# RP2040.net
KiCad netlist of a schematic drawn in Altium Designer
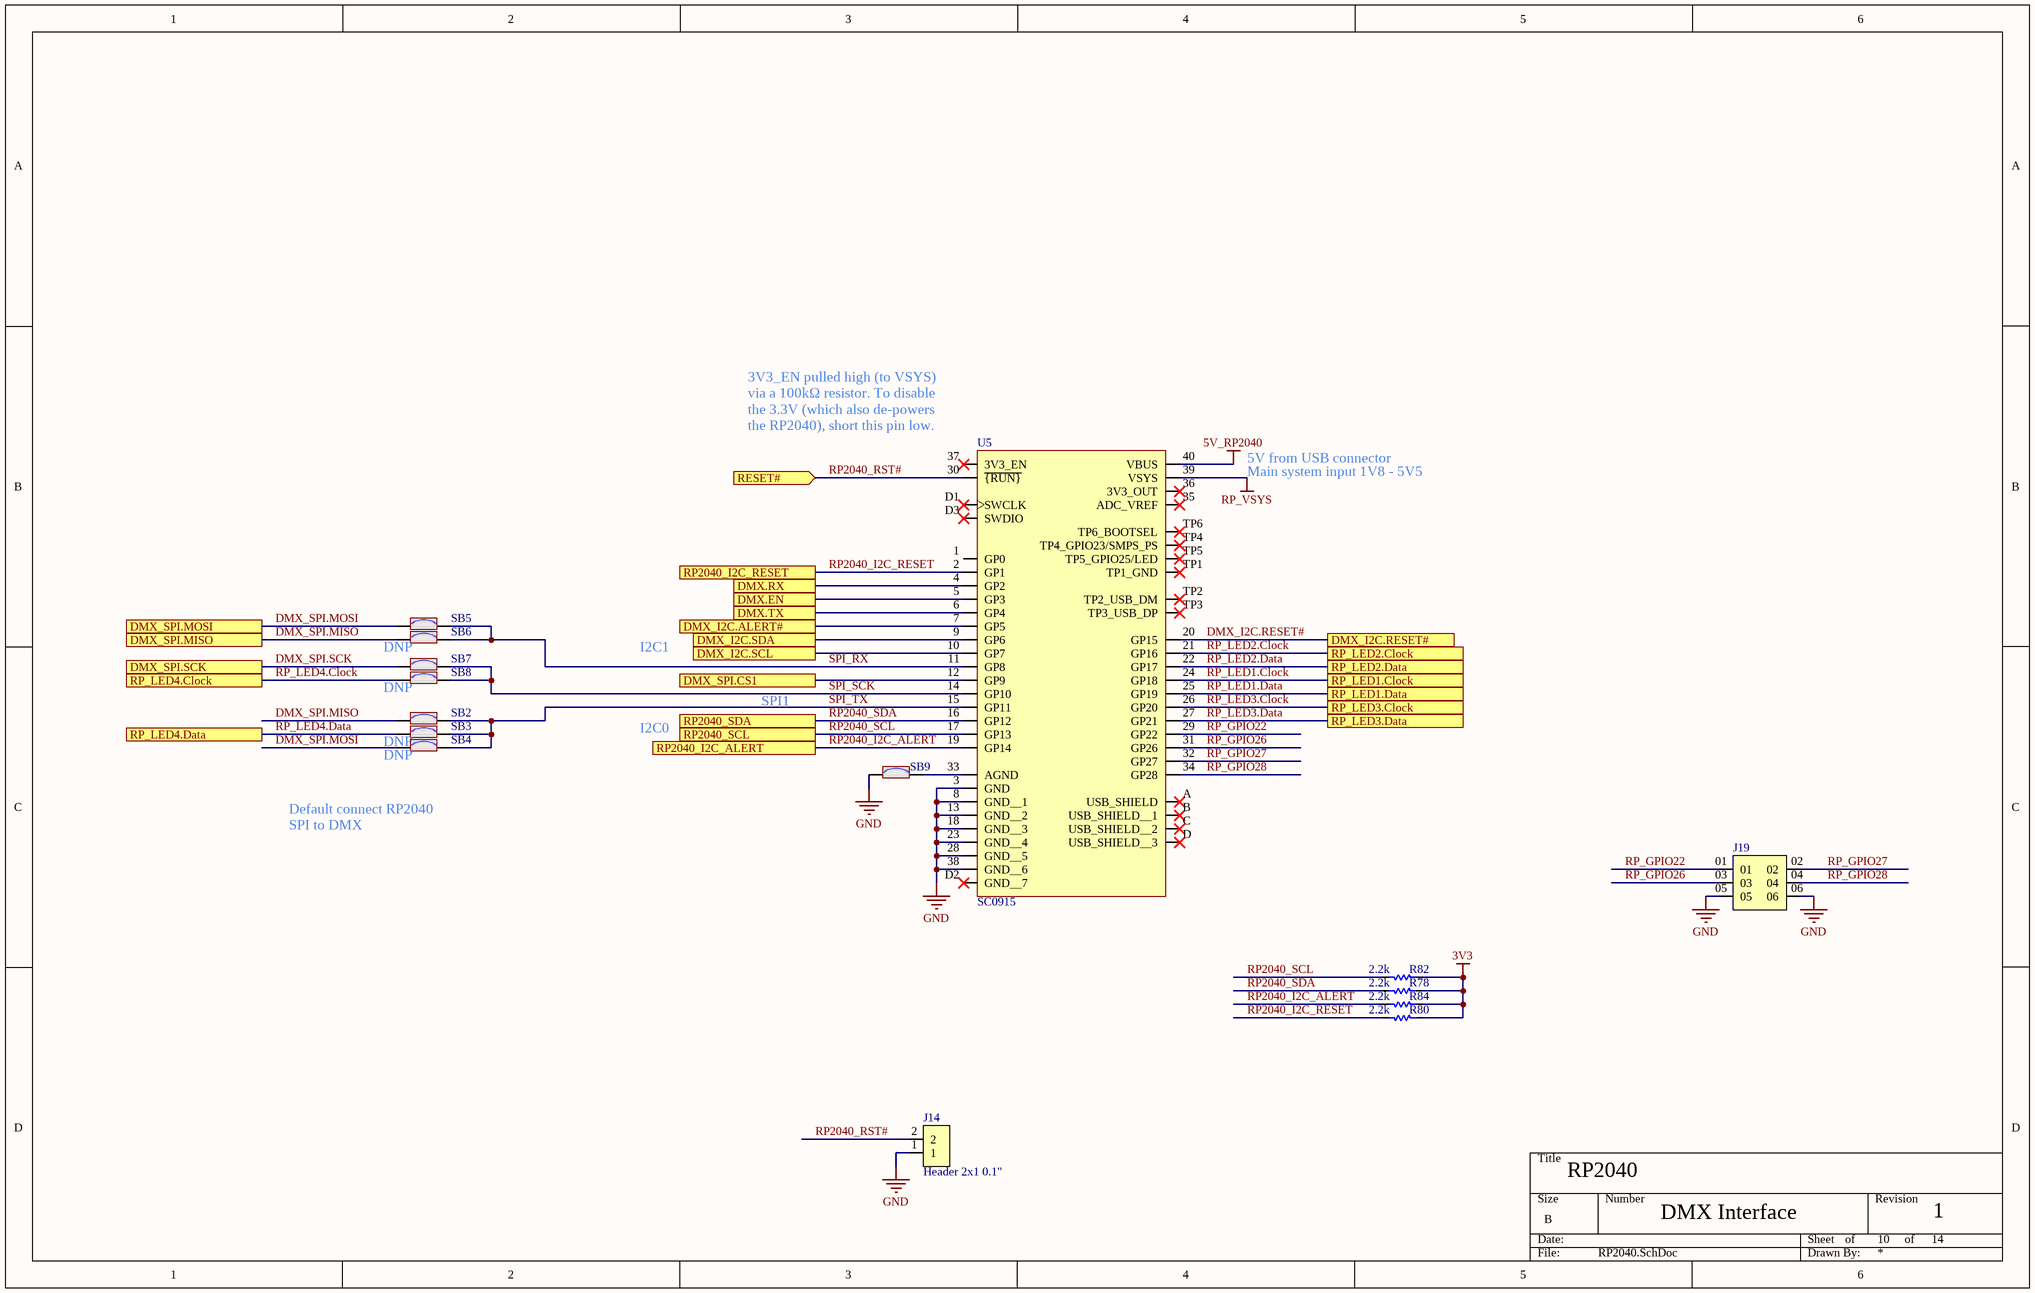
[diagram p0: RP2040.SchDoc]

(export (version "E")
  (design (tool "Eeschema 10.0.6"))
  (components
    (comp (ref "J14")
      (value "Header 2x1 0.1\"")
      (footprint "FP-M20-9990245-MFG")
      (description "Conn Header Vert 2POS 2.54MM")
      (libsource (lib "Equus Computer Systems") (part "HEADER-2x1"))
    )
    (comp (ref "J19")
      (value "Header 3x2 0.1\"")
      (footprint "HEADER 3x2 0.1 Through hole")
      (description "Board Connector Tall, 6 Contact(s), 2 Row(s), Male, Straight, 0.1 inch Pitch")
      (libsource (lib "Equus Computer Systems") (part "Header 3x2 0.1{dblquote}"))
    )
    (comp (ref "R78")
      (value "2.2k")
      (footprint "RESC1608X06N_0603_MED")
      (fields
        (field (name "TOLERANCE") "1%")
        (field (name "POWER") "100mW")
        (field (name "Comment") "RC0603FR-072K2L")
      )
      (libsource (lib "Equus Computer Systems") (part "RES-2"))
    )
    (comp (ref "R80")
      (value "2.2k")
      (footprint "RESC1608X06N_0603_MED")
      (fields
        (field (name "TOLERANCE") "1%")
        (field (name "POWER") "100mW")
        (field (name "Comment") "RC0603FR-072K2L")
      )
      (libsource (lib "Equus Computer Systems") (part "RES-2"))
    )
    (comp (ref "R82")
      (value "2.2k")
      (footprint "RESC1608X06N_0603_MED")
      (fields
        (field (name "TOLERANCE") "1%")
        (field (name "POWER") "100mW")
        (field (name "Comment") "RC0603FR-072K2L")
      )
      (libsource (lib "Equus Computer Systems") (part "RES-2"))
    )
    (comp (ref "R84")
      (value "2.2k")
      (footprint "RESC1608X06N_0603_MED")
      (fields
        (field (name "TOLERANCE") "1%")
        (field (name "POWER") "100mW")
        (field (name "Comment") "RC0603FR-072K2L")
      )
      (libsource (lib "Equus Computer Systems") (part "RES-2"))
    )
    (comp (ref "SB2")
      (value "SolderBridge0603_On")
      (footprint "SOLDER-BRIDGE_R0603-0R-CLOSEMASK")
      (description "Solder Bridge ON")
      (fields
        (field (name "INTERNAL_PART_NUMBER") "MCD-00071")
        (field (name "MANUFACTURER") "YAGEO")
        (field (name "PROVIDED_BY") "SUBCO")
      )
      (libsource (lib "Equus Computer Systems") (part "SolderBridge0603_On"))
    )
    (comp (ref "SB3")
      (value "SolderBridge0603_On")
      (footprint "SOLDER-BRIDGE_R0603-0R-CLOSEMASK")
      (description "Solder Bridge ON")
      (fields
        (field (name "INTERNAL_PART_NUMBER") "MCD-00071")
        (field (name "MANUFACTURER") "YAGEO")
        (field (name "PROVIDED_BY") "SUBCO")
      )
      (libsource (lib "Equus Computer Systems") (part "SolderBridge0603_On"))
    )
    (comp (ref "SB4")
      (value "SolderBridge0603_On")
      (footprint "SOLDER-BRIDGE_R0603-0R-CLOSEMASK")
      (description "Solder Bridge ON")
      (fields
        (field (name "INTERNAL_PART_NUMBER") "MCD-00071")
        (field (name "MANUFACTURER") "YAGEO")
        (field (name "PROVIDED_BY") "SUBCO")
      )
      (libsource (lib "Equus Computer Systems") (part "SolderBridge0603_On"))
    )
    (comp (ref "SB5")
      (value "SolderBridge0603_On")
      (footprint "SOLDER-BRIDGE_R0603-0R-CLOSEMASK")
      (description "Solder Bridge ON")
      (fields
        (field (name "INTERNAL_PART_NUMBER") "MCD-00071")
        (field (name "MANUFACTURER") "YAGEO")
        (field (name "PROVIDED_BY") "SUBCO")
      )
      (libsource (lib "Equus Computer Systems") (part "SolderBridge0603_On"))
    )
    (comp (ref "SB6")
      (value "SolderBridge0603_On")
      (footprint "SOLDER-BRIDGE_R0603-0R-CLOSEMASK")
      (description "Solder Bridge ON")
      (fields
        (field (name "INTERNAL_PART_NUMBER") "MCD-00071")
        (field (name "MANUFACTURER") "YAGEO")
        (field (name "PROVIDED_BY") "SUBCO")
      )
      (libsource (lib "Equus Computer Systems") (part "SolderBridge0603_On"))
    )
    (comp (ref "SB7")
      (value "SolderBridge0603_On")
      (footprint "SOLDER-BRIDGE_R0603-0R-CLOSEMASK")
      (description "Solder Bridge ON")
      (fields
        (field (name "INTERNAL_PART_NUMBER") "MCD-00071")
        (field (name "MANUFACTURER") "YAGEO")
        (field (name "PROVIDED_BY") "SUBCO")
      )
      (libsource (lib "Equus Computer Systems") (part "SolderBridge0603_On"))
    )
    (comp (ref "SB8")
      (value "SolderBridge0603_On")
      (footprint "SOLDER-BRIDGE_R0603-0R-CLOSEMASK")
      (description "Solder Bridge ON")
      (fields
        (field (name "INTERNAL_PART_NUMBER") "MCD-00071")
        (field (name "MANUFACTURER") "YAGEO")
        (field (name "PROVIDED_BY") "SUBCO")
      )
      (libsource (lib "Equus Computer Systems") (part "SolderBridge0603_On"))
    )
    (comp (ref "SB9")
      (value "SolderBridge0603_On")
      (footprint "SOLDER-BRIDGE_R0603-0R")
      (description "Solder Bridge ON")
      (fields
        (field (name "INTERNAL_PART_NUMBER") "MCD-00071")
        (field (name "MANUFACTURER") "YAGEO")
        (field (name "PROVIDED_BY") "SUBCO")
      )
      (libsource (lib "Equus Computer Systems") (part "SolderBridge0603_On"))
    )
    (comp (ref "U5")
      (value "SC0915")
      (footprint "SC0915-Footprint-NoDEBUG")
      (description "RP2040 Pico ARM Cortex-M0+ - Microcontroller IC 32-Bit Dual-Core 133MHz")
      (fields (field (name "MF") "Raspberry Pi"))
      (libsource (lib "Equus Computer Systems") (part "SC0915-Symbol-1"))
    )
  )
  (nets
    (net (code "1") (name "/DMX.EN") (class "Default")
      (node (ref "U5") (pin "5") (pinfunction "GP3_5") (pintype "passive"))
    )
    (net (code "2") (name "/DMX.RX") (class "Default")
      (node (ref "U5") (pin "4") (pinfunction "GP2_4") (pintype "passive"))
    )
    (net (code "3") (name "/DMX.TX") (class "Default")
      (node (ref "U5") (pin "6") (pinfunction "GP4_6") (pintype "passive"))
    )
    (net (code "4") (name "/DMX_I2C.ALERT#") (class "Default")
      (node (ref "U5") (pin "7") (pinfunction "GP5_7") (pintype "passive"))
    )
    (net (code "5") (name "/DMX_I2C.RESET#") (class "Default")
      (node (ref "U5") (pin "20") (pinfunction "GP15_20") (pintype "passive"))
    )
    (net (code "6") (name "/DMX_I2C.SCL") (class "Default")
      (node (ref "U5") (pin "10") (pinfunction "GP7_10") (pintype "passive"))
    )
    (net (code "7") (name "/DMX_I2C.SDA") (class "Default")
      (node (ref "U5") (pin "9") (pinfunction "GP6_9") (pintype "passive"))
    )
    (net (code "8") (name "/DMX_SPI.CS1") (class "Default")
      (node (ref "U5") (pin "12") (pinfunction "GP9_12") (pintype "passive"))
    )
    (net (code "9") (name "/DMX_SPI.MISO") (class "Default")
      (node (ref "SB2") (pin "1") (pinfunction "1_1") (pintype "passive"))
      (node (ref "SB6") (pin "1") (pinfunction "1_1") (pintype "passive"))
    )
    (net (code "10") (name "/DMX_SPI.MOSI") (class "Default")
      (node (ref "SB4") (pin "1") (pinfunction "1_1") (pintype "passive"))
      (node (ref "SB5") (pin "1") (pinfunction "1_1") (pintype "passive"))
    )
    (net (code "11") (name "/DMX_SPI.SCK") (class "Default")
      (node (ref "SB7") (pin "1") (pinfunction "1_1") (pintype "passive"))
    )
    (net (code "12") (name "/RP2040_I2C_ALERT") (class "Default")
      (node (ref "R84") (pin "1") (pinfunction "1_1") (pintype "passive"))
      (node (ref "U5") (pin "19") (pinfunction "GP14_19") (pintype "passive"))
    )
    (net (code "13") (name "/RP2040_I2C_RESET") (class "Default")
      (node (ref "R80") (pin "1") (pinfunction "1_1") (pintype "passive"))
      (node (ref "U5") (pin "2") (pinfunction "GP1_2") (pintype "passive"))
    )
    (net (code "14") (name "/RP2040_RST#") (class "Default")
      (node (ref "J14") (pin "2") (pinfunction "2_2") (pintype "passive"))
      (node (ref "U5") (pin "30") (pinfunction "~{{RUN}}_30") (pintype "passive"))
    )
    (net (code "15") (name "/RP2040_SCL") (class "Default")
      (node (ref "R82") (pin "1") (pinfunction "1_1") (pintype "passive"))
      (node (ref "U5") (pin "17") (pinfunction "GP13_17") (pintype "passive"))
    )
    (net (code "16") (name "/RP2040_SDA") (class "Default")
      (node (ref "R78") (pin "1") (pinfunction "1_1") (pintype "passive"))
      (node (ref "U5") (pin "16") (pinfunction "GP12_16") (pintype "passive"))
    )
    (net (code "17") (name "/RP_GPIO22") (class "Default")
      (node (ref "J19") (pin "01") (pinfunction "01_01") (pintype "passive"))
      (node (ref "U5") (pin "29") (pinfunction "GP22_29") (pintype "passive"))
    )
    (net (code "18") (name "/RP_GPIO26") (class "Default")
      (node (ref "J19") (pin "03") (pinfunction "03_03") (pintype "passive"))
      (node (ref "U5") (pin "31") (pinfunction "GP26_31") (pintype "passive"))
    )
    (net (code "19") (name "/RP_GPIO27") (class "Default")
      (node (ref "J19") (pin "02") (pinfunction "02_02") (pintype "passive"))
      (node (ref "U5") (pin "32") (pinfunction "GP27_32") (pintype "passive"))
    )
    (net (code "20") (name "/RP_GPIO28") (class "Default")
      (node (ref "J19") (pin "04") (pinfunction "04_04") (pintype "passive"))
      (node (ref "U5") (pin "34") (pinfunction "GP28_34") (pintype "passive"))
    )
    (net (code "21") (name "/RP_LED1.Clock") (class "Default")
      (node (ref "U5") (pin "24") (pinfunction "GP18_24") (pintype "passive"))
    )
    (net (code "22") (name "/RP_LED1.Data") (class "Default")
      (node (ref "U5") (pin "25") (pinfunction "GP19_25") (pintype "passive"))
    )
    (net (code "23") (name "/RP_LED2.Clock") (class "Default")
      (node (ref "U5") (pin "21") (pinfunction "GP16_21") (pintype "passive"))
    )
    (net (code "24") (name "/RP_LED2.Data") (class "Default")
      (node (ref "U5") (pin "22") (pinfunction "GP17_22") (pintype "passive"))
    )
    (net (code "25") (name "/RP_LED3.Clock") (class "Default")
      (node (ref "U5") (pin "26") (pinfunction "GP20_26") (pintype "passive"))
    )
    (net (code "26") (name "/RP_LED3.Data") (class "Default")
      (node (ref "U5") (pin "27") (pinfunction "GP21_27") (pintype "passive"))
    )
    (net (code "27") (name "/RP_LED4.Clock") (class "Default")
      (node (ref "SB8") (pin "1") (pinfunction "1_1") (pintype "passive"))
    )
    (net (code "28") (name "/RP_LED4.Data") (class "Default")
      (node (ref "SB3") (pin "1") (pinfunction "1_1") (pintype "passive"))
    )
    (net (code "29") (name "/SPI_RX") (class "Default")
      (node (ref "SB5") (pin "2") (pinfunction "2_2") (pintype "passive"))
      (node (ref "SB6") (pin "2") (pinfunction "2_2") (pintype "passive"))
      (node (ref "U5") (pin "11") (pinfunction "GP8_11") (pintype "passive"))
    )
    (net (code "30") (name "/SPI_SCK") (class "Default")
      (node (ref "SB7") (pin "2") (pinfunction "2_2") (pintype "passive"))
      (node (ref "SB8") (pin "2") (pinfunction "2_2") (pintype "passive"))
      (node (ref "U5") (pin "14") (pinfunction "GP10_14") (pintype "passive"))
    )
    (net (code "31") (name "/SPI_TX") (class "Default")
      (node (ref "SB2") (pin "2") (pinfunction "2_2") (pintype "passive"))
      (node (ref "SB3") (pin "2") (pinfunction "2_2") (pintype "passive"))
      (node (ref "SB4") (pin "2") (pinfunction "2_2") (pintype "passive"))
      (node (ref "U5") (pin "15") (pinfunction "GP11_15") (pintype "passive"))
    )
    (net (code "32") (name "3V3") (class "Default")
      (node (ref "R78") (pin "2") (pinfunction "2_2") (pintype "passive"))
      (node (ref "R80") (pin "2") (pinfunction "2_2") (pintype "passive"))
      (node (ref "R82") (pin "2") (pinfunction "2_2") (pintype "passive"))
      (node (ref "R84") (pin "2") (pinfunction "2_2") (pintype "passive"))
    )
    (net (code "33") (name "5V_RP2040") (class "Default")
      (node (ref "U5") (pin "40") (pinfunction "VBUS_40") (pintype "passive"))
    )
    (net (code "34") (name "GND") (class "Default")
      (node (ref "J14") (pin "1") (pinfunction "1_1") (pintype "passive"))
      (node (ref "J19") (pin "05") (pinfunction "05_05") (pintype "passive"))
      (node (ref "J19") (pin "06") (pinfunction "06_06") (pintype "passive"))
      (node (ref "SB9") (pin "1") (pinfunction "1_1") (pintype "passive"))
      (node (ref "U5") (pin "13") (pinfunction "GND__2_13") (pintype "passive"))
      (node (ref "U5") (pin "18") (pinfunction "GND__3_18") (pintype "passive"))
      (node (ref "U5") (pin "23") (pinfunction "GND__4_23") (pintype "passive"))
      (node (ref "U5") (pin "28") (pinfunction "GND__5_28") (pintype "passive"))
      (node (ref "U5") (pin "3") (pinfunction "GND_3") (pintype "passive"))
      (node (ref "U5") (pin "38") (pinfunction "GND__6_38") (pintype "passive"))
      (node (ref "U5") (pin "8") (pinfunction "GND__1_8") (pintype "passive"))
    )
    (net (code "35") (name "Net-(U5-AGND)") (class "Default")
      (node (ref "SB9") (pin "2") (pinfunction "2_2") (pintype "passive"))
      (node (ref "U5") (pin "33") (pinfunction "AGND_33") (pintype "passive"))
    )
    (net (code "36") (name "RP_VSYS") (class "Default")
      (node (ref "U5") (pin "39") (pinfunction "VSYS_39") (pintype "passive"))
    )
    (net (code "37") (name "unconnected-(U5-3V3_EN-Pad37)") (class "Default")
      (node (ref "U5") (pin "37") (pinfunction "3V3_EN_37") (pintype "passive+no_connect"))
    )
    (net (code "38") (name "unconnected-(U5-3V3_OUT-Pad36)") (class "Default")
      (node (ref "U5") (pin "36") (pinfunction "3V3_OUT_36") (pintype "passive+no_connect"))
    )
    (net (code "39") (name "unconnected-(U5-ADC_VREF-Pad35)") (class "Default")
      (node (ref "U5") (pin "35") (pinfunction "ADC_VREF_35") (pintype "passive+no_connect"))
    )
    (net (code "40") (name "unconnected-(U5-GND__7-PadD2)") (class "Default")
      (node (ref "U5") (pin "D2") (pinfunction "GND__7_D2") (pintype "passive+no_connect"))
    )
    (net (code "41") (name "unconnected-(U5-GP0-Pad1)") (class "Default")
      (node (ref "U5") (pin "1") (pinfunction "GP0_1") (pintype "passive"))
    )
    (net (code "42") (name "unconnected-(U5-SWCLK-PadD1)") (class "Default")
      (node (ref "U5") (pin "D1") (pinfunction "SWCLK_D1") (pintype "passive+no_connect"))
    )
    (net (code "43") (name "unconnected-(U5-SWDIO-PadD3)") (class "Default")
      (node (ref "U5") (pin "D3") (pinfunction "SWDIO_D3") (pintype "passive+no_connect"))
    )
    (net (code "44") (name "unconnected-(U5-TP1_GND-PadTP1)") (class "Default")
      (node (ref "U5") (pin "TP1") (pinfunction "TP1_GND_TP1") (pintype "passive+no_connect"))
    )
    (net (code "45") (name "unconnected-(U5-TP2_USB_DM-PadTP2)") (class "Default")
      (node (ref "U5") (pin "TP2") (pinfunction "TP2_USB_DM_TP2") (pintype "passive+no_connect"))
    )
    (net (code "46") (name "unconnected-(U5-TP3_USB_DP-PadTP3)") (class "Default")
      (node (ref "U5") (pin "TP3") (pinfunction "TP3_USB_DP_TP3") (pintype "passive+no_connect"))
    )
    (net (code "47") (name "unconnected-(U5-TP4_GPIO23{slash}SMPS_PS-PadTP4)") (class "Default")
      (node (ref "U5") (pin "TP4") (pinfunction "TP4_GPIO23/SMPS_PS_TP4") (pintype "passive+no_connect"))
    )
    (net (code "48") (name "unconnected-(U5-TP5_GPIO25{slash}LED-PadTP5)") (class "Default")
      (node (ref "U5") (pin "TP5") (pinfunction "TP5_GPIO25/LED_TP5") (pintype "passive+no_connect"))
    )
    (net (code "49") (name "unconnected-(U5-TP6_BOOTSEL-PadTP6)") (class "Default")
      (node (ref "U5") (pin "TP6") (pinfunction "TP6_BOOTSEL_TP6") (pintype "passive+no_connect"))
    )
    (net (code "50") (name "unconnected-(U5-USB_SHIELD-PadA)") (class "Default")
      (node (ref "U5") (pin "A") (pinfunction "USB_SHIELD_A") (pintype "passive+no_connect"))
    )
    (net (code "51") (name "unconnected-(U5-USB_SHIELD__1-PadB)") (class "Default")
      (node (ref "U5") (pin "B") (pinfunction "USB_SHIELD__1_B") (pintype "passive+no_connect"))
    )
    (net (code "52") (name "unconnected-(U5-USB_SHIELD__2-PadC)") (class "Default")
      (node (ref "U5") (pin "C") (pinfunction "USB_SHIELD__2_C") (pintype "passive+no_connect"))
    )
    (net (code "53") (name "unconnected-(U5-USB_SHIELD__3-PadD)") (class "Default")
      (node (ref "U5") (pin "D") (pinfunction "USB_SHIELD__3_D") (pintype "passive+no_connect"))
    )
  )
)
